# 2022_AESK_UAV_CONNECTOR.net
KiCad netlist of a schematic drawn in Altium Designer
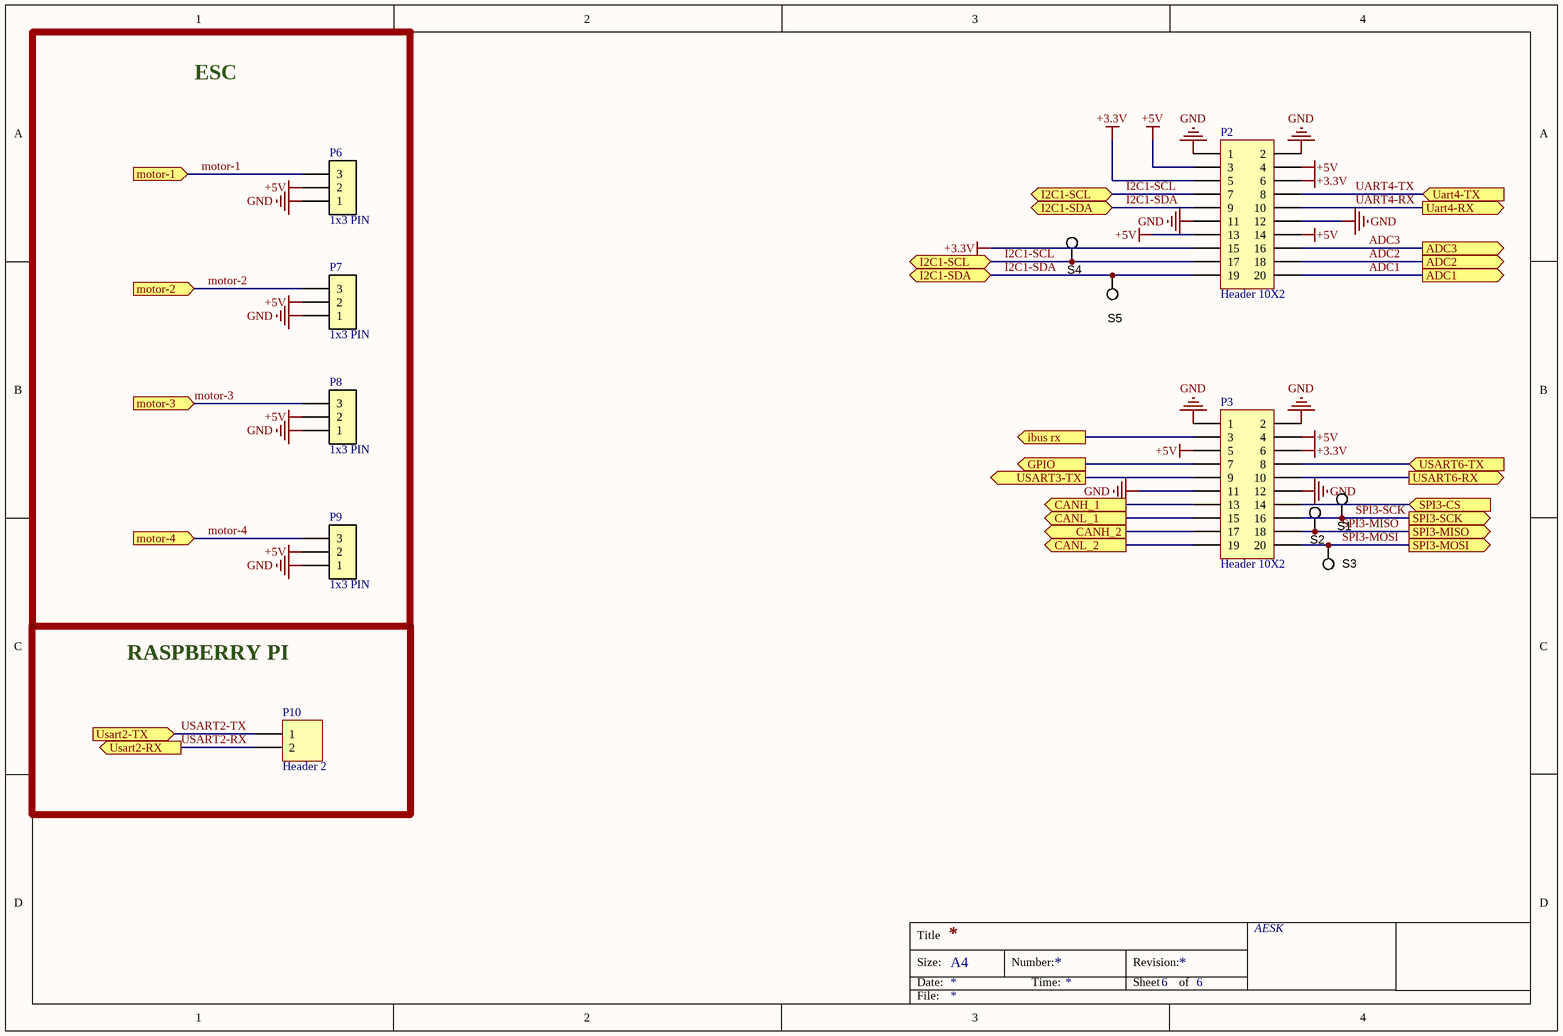
[diagram p0: 2022_AESK_UAV_CONNECTOR.SchDoc]

(export (version "E")
  (design (tool "Eeschema 10.0.6"))
  (components
    (comp (ref "P2")
      (value "Header 10X2")
      (footprint "HDR2X10")
      (description "Header, 10-Pin, Dual row")
      (fields (field (name "PUBLISHER") "Altium Limited"))
      (libsource (lib "Miscellaneous Connectors") (part "Header 10X2"))
    )
    (comp (ref "P3")
      (value "Header 10X2")
      (footprint "HDR2X10")
      (description "Header, 10-Pin, Dual row")
      (fields (field (name "PUBLISHER") "Altium Limited"))
      (libsource (lib "Miscellaneous Connectors") (part "Header 10X2"))
    )
    (comp (ref "P6")
      (value "1x3 PIN")
      (footprint "HDR_2.54_1X3")
      (description "Header 2.54 1x3")
      (fields (field (name "PART NUMBER") "Connector0009"))
      (libsource (lib "AESK Database Library") (part "1x3 PIN"))
    )
    (comp (ref "P7")
      (value "1x3 PIN")
      (footprint "HDR_2.54_1X3")
      (description "Header 2.54 1x3")
      (fields (field (name "PART NUMBER") "Connector0009"))
      (libsource (lib "AESK Database Library") (part "1x3 PIN"))
    )
    (comp (ref "P8")
      (value "1x3 PIN")
      (footprint "HDR_2.54_1X3")
      (description "Header 2.54 1x3")
      (fields (field (name "PART NUMBER") "Connector0009"))
      (libsource (lib "AESK Database Library") (part "1x3 PIN"))
    )
    (comp (ref "P9")
      (value "1x3 PIN")
      (footprint "HDR_2.54_1X3")
      (description "Header 2.54 1x3")
      (fields (field (name "PART NUMBER") "Connector0009"))
      (libsource (lib "AESK Database Library") (part "1x3 PIN"))
    )
    (comp (ref "P10")
      (value "Header 2")
      (footprint "HDR1X2")
      (description "Header, 2-Pin")
      (fields (field (name "PUBLISHER") "Altium Limited"))
      (libsource (lib "Miscellaneous Connectors") (part "Header 2"))
    )
    (comp (ref "S1")
      (value "5002")
      (footprint "Keystone5002")
      (description "Test Point, TH, Miniature, White")
      (fields
        (field (name "MANUFACTURER") "Keystone")
        (field (name "DIGIKEYPARTNUMBER") "5002K-ND")
        (field (name "PUBLISHER") "National Semiconductor")
      )
      (libsource (lib "2022_AESK_UAV") (part "5002"))
    )
    (comp (ref "S2")
      (value "5002")
      (footprint "Keystone5002")
      (description "Test Point, TH, Miniature, White")
      (fields
        (field (name "MANUFACTURER") "Keystone")
        (field (name "DIGIKEYPARTNUMBER") "5002K-ND")
        (field (name "PUBLISHER") "National Semiconductor")
      )
      (libsource (lib "2022_AESK_UAV") (part "5002"))
    )
    (comp (ref "S3")
      (value "5002")
      (footprint "Keystone5002")
      (description "Test Point, TH, Miniature, White")
      (fields
        (field (name "MANUFACTURER") "Keystone")
        (field (name "DIGIKEYPARTNUMBER") "5002K-ND")
        (field (name "PUBLISHER") "National Semiconductor")
      )
      (libsource (lib "2022_AESK_UAV") (part "5002"))
    )
    (comp (ref "S4")
      (value "5002")
      (footprint "Keystone5002")
      (description "Test Point, TH, Miniature, White")
      (fields
        (field (name "MANUFACTURER") "Keystone")
        (field (name "DIGIKEYPARTNUMBER") "5002K-ND")
        (field (name "PUBLISHER") "National Semiconductor")
      )
      (libsource (lib "2022_AESK_UAV") (part "5002"))
    )
    (comp (ref "S5")
      (value "5002")
      (footprint "Keystone5002")
      (description "Test Point, TH, Miniature, White")
      (fields
        (field (name "MANUFACTURER") "Keystone")
        (field (name "DIGIKEYPARTNUMBER") "5002K-ND")
        (field (name "PUBLISHER") "National Semiconductor")
      )
      (libsource (lib "2022_AESK_UAV") (part "5002"))
    )
  )
  (nets
    (net (code "1") (name "+3.3V") (class "Default")
      (node (ref "P2") (pin "15") (pinfunction "15_15") (pintype "passive"))
      (node (ref "P2") (pin "5") (pinfunction "5_5") (pintype "passive"))
      (node (ref "P2") (pin "6") (pinfunction "6_6") (pintype "passive"))
      (node (ref "P3") (pin "6") (pinfunction "6_6") (pintype "passive"))
    )
    (net (code "2") (name "+5V") (class "Default")
      (node (ref "P2") (pin "13") (pinfunction "13_13") (pintype "passive"))
      (node (ref "P2") (pin "14") (pinfunction "14_14") (pintype "passive"))
      (node (ref "P2") (pin "3") (pinfunction "3_3") (pintype "passive"))
      (node (ref "P2") (pin "4") (pinfunction "4_4") (pintype "passive"))
      (node (ref "P3") (pin "4") (pinfunction "4_4") (pintype "passive"))
      (node (ref "P3") (pin "5") (pinfunction "5_5") (pintype "passive"))
      (node (ref "P6") (pin "2") (pinfunction "2_2") (pintype "passive"))
      (node (ref "P7") (pin "2") (pinfunction "2_2") (pintype "passive"))
      (node (ref "P8") (pin "2") (pinfunction "2_2") (pintype "passive"))
      (node (ref "P9") (pin "2") (pinfunction "2_2") (pintype "passive"))
    )
    (net (code "3") (name "/ADC1") (class "Default")
      (node (ref "P2") (pin "20") (pinfunction "20_20") (pintype "passive"))
    )
    (net (code "4") (name "/ADC2") (class "Default")
      (node (ref "P2") (pin "18") (pinfunction "18_18") (pintype "passive"))
    )
    (net (code "5") (name "/ADC3") (class "Default")
      (node (ref "P2") (pin "16") (pinfunction "16_16") (pintype "passive"))
    )
    (net (code "6") (name "/CANH_1") (class "Default")
      (node (ref "P3") (pin "13") (pinfunction "13_13") (pintype "passive"))
    )
    (net (code "7") (name "/CANH_2") (class "Default")
      (node (ref "P3") (pin "17") (pinfunction "17_17") (pintype "passive"))
    )
    (net (code "8") (name "/CANL_1") (class "Default")
      (node (ref "P3") (pin "15") (pinfunction "15_15") (pintype "passive"))
    )
    (net (code "9") (name "/CANL_2") (class "Default")
      (node (ref "P3") (pin "19") (pinfunction "19_19") (pintype "passive"))
    )
    (net (code "10") (name "/GPIO") (class "Default")
      (node (ref "P3") (pin "7") (pinfunction "7_7") (pintype "passive"))
    )
    (net (code "11") (name "/I2C1-SCL") (class "Default")
      (node (ref "P2") (pin "17") (pinfunction "17_17") (pintype "passive"))
      (node (ref "P2") (pin "7") (pinfunction "7_7") (pintype "passive"))
      (node (ref "S4") (pin "1") (pintype "passive"))
    )
    (net (code "12") (name "/I2C1-SDA") (class "Default")
      (node (ref "P2") (pin "19") (pinfunction "19_19") (pintype "passive"))
      (node (ref "P2") (pin "9") (pinfunction "9_9") (pintype "passive"))
      (node (ref "S5") (pin "1") (pintype "passive"))
    )
    (net (code "13") (name "/SPI3-CS") (class "Default")
      (node (ref "P3") (pin "14") (pinfunction "14_14") (pintype "passive"))
    )
    (net (code "14") (name "/SPI3-MISO") (class "Default")
      (node (ref "P3") (pin "18") (pinfunction "18_18") (pintype "passive"))
      (node (ref "S2") (pin "1") (pintype "passive"))
    )
    (net (code "15") (name "/SPI3-MOSI") (class "Default")
      (node (ref "P3") (pin "20") (pinfunction "20_20") (pintype "passive"))
      (node (ref "S3") (pin "1") (pintype "passive"))
    )
    (net (code "16") (name "/SPI3-SCK") (class "Default")
      (node (ref "P3") (pin "16") (pinfunction "16_16") (pintype "passive"))
      (node (ref "S1") (pin "1") (pintype "passive"))
    )
    (net (code "17") (name "/UART4-RX") (class "Default")
      (node (ref "P2") (pin "10") (pinfunction "10_10") (pintype "passive"))
    )
    (net (code "18") (name "/UART4-TX") (class "Default")
      (node (ref "P2") (pin "8") (pinfunction "8_8") (pintype "passive"))
    )
    (net (code "19") (name "/USART2-RX") (class "Default")
      (node (ref "P10") (pin "2") (pinfunction "2_2") (pintype "passive"))
    )
    (net (code "20") (name "/USART2-TX") (class "Default")
      (node (ref "P10") (pin "1") (pinfunction "1_1") (pintype "passive"))
    )
    (net (code "21") (name "/USART3-TX") (class "Default")
      (node (ref "P3") (pin "9") (pinfunction "9_9") (pintype "passive"))
    )
    (net (code "22") (name "/USART6-RX") (class "Default")
      (node (ref "P3") (pin "10") (pinfunction "10_10") (pintype "passive"))
    )
    (net (code "23") (name "/USART6-TX") (class "Default")
      (node (ref "P3") (pin "8") (pinfunction "8_8") (pintype "passive"))
    )
    (net (code "24") (name "/ibus rx") (class "Default")
      (node (ref "P3") (pin "3") (pinfunction "3_3") (pintype "passive"))
    )
    (net (code "25") (name "/motor-1") (class "Default")
      (node (ref "P6") (pin "3") (pinfunction "3_3") (pintype "passive"))
    )
    (net (code "26") (name "/motor-2") (class "Default")
      (node (ref "P7") (pin "3") (pinfunction "3_3") (pintype "passive"))
    )
    (net (code "27") (name "/motor-3") (class "Default")
      (node (ref "P8") (pin "3") (pinfunction "3_3") (pintype "passive"))
    )
    (net (code "28") (name "/motor-4") (class "Default")
      (node (ref "P9") (pin "3") (pinfunction "3_3") (pintype "passive"))
    )
    (net (code "29") (name "GND") (class "Default")
      (node (ref "P2") (pin "1") (pinfunction "1_1") (pintype "passive"))
      (node (ref "P2") (pin "11") (pinfunction "11_11") (pintype "passive"))
      (node (ref "P2") (pin "12") (pinfunction "12_12") (pintype "passive"))
      (node (ref "P2") (pin "2") (pinfunction "2_2") (pintype "passive"))
      (node (ref "P3") (pin "1") (pinfunction "1_1") (pintype "passive"))
      (node (ref "P3") (pin "11") (pinfunction "11_11") (pintype "passive"))
      (node (ref "P3") (pin "12") (pinfunction "12_12") (pintype "passive"))
      (node (ref "P3") (pin "2") (pinfunction "2_2") (pintype "passive"))
      (node (ref "P6") (pin "1") (pinfunction "1_1") (pintype "passive"))
      (node (ref "P7") (pin "1") (pinfunction "1_1") (pintype "passive"))
      (node (ref "P8") (pin "1") (pinfunction "1_1") (pintype "passive"))
      (node (ref "P9") (pin "1") (pinfunction "1_1") (pintype "passive"))
    )
  )
)
